# LTC4150_BOB.net
KiCad netlist of a schematic drawn in EAGLE
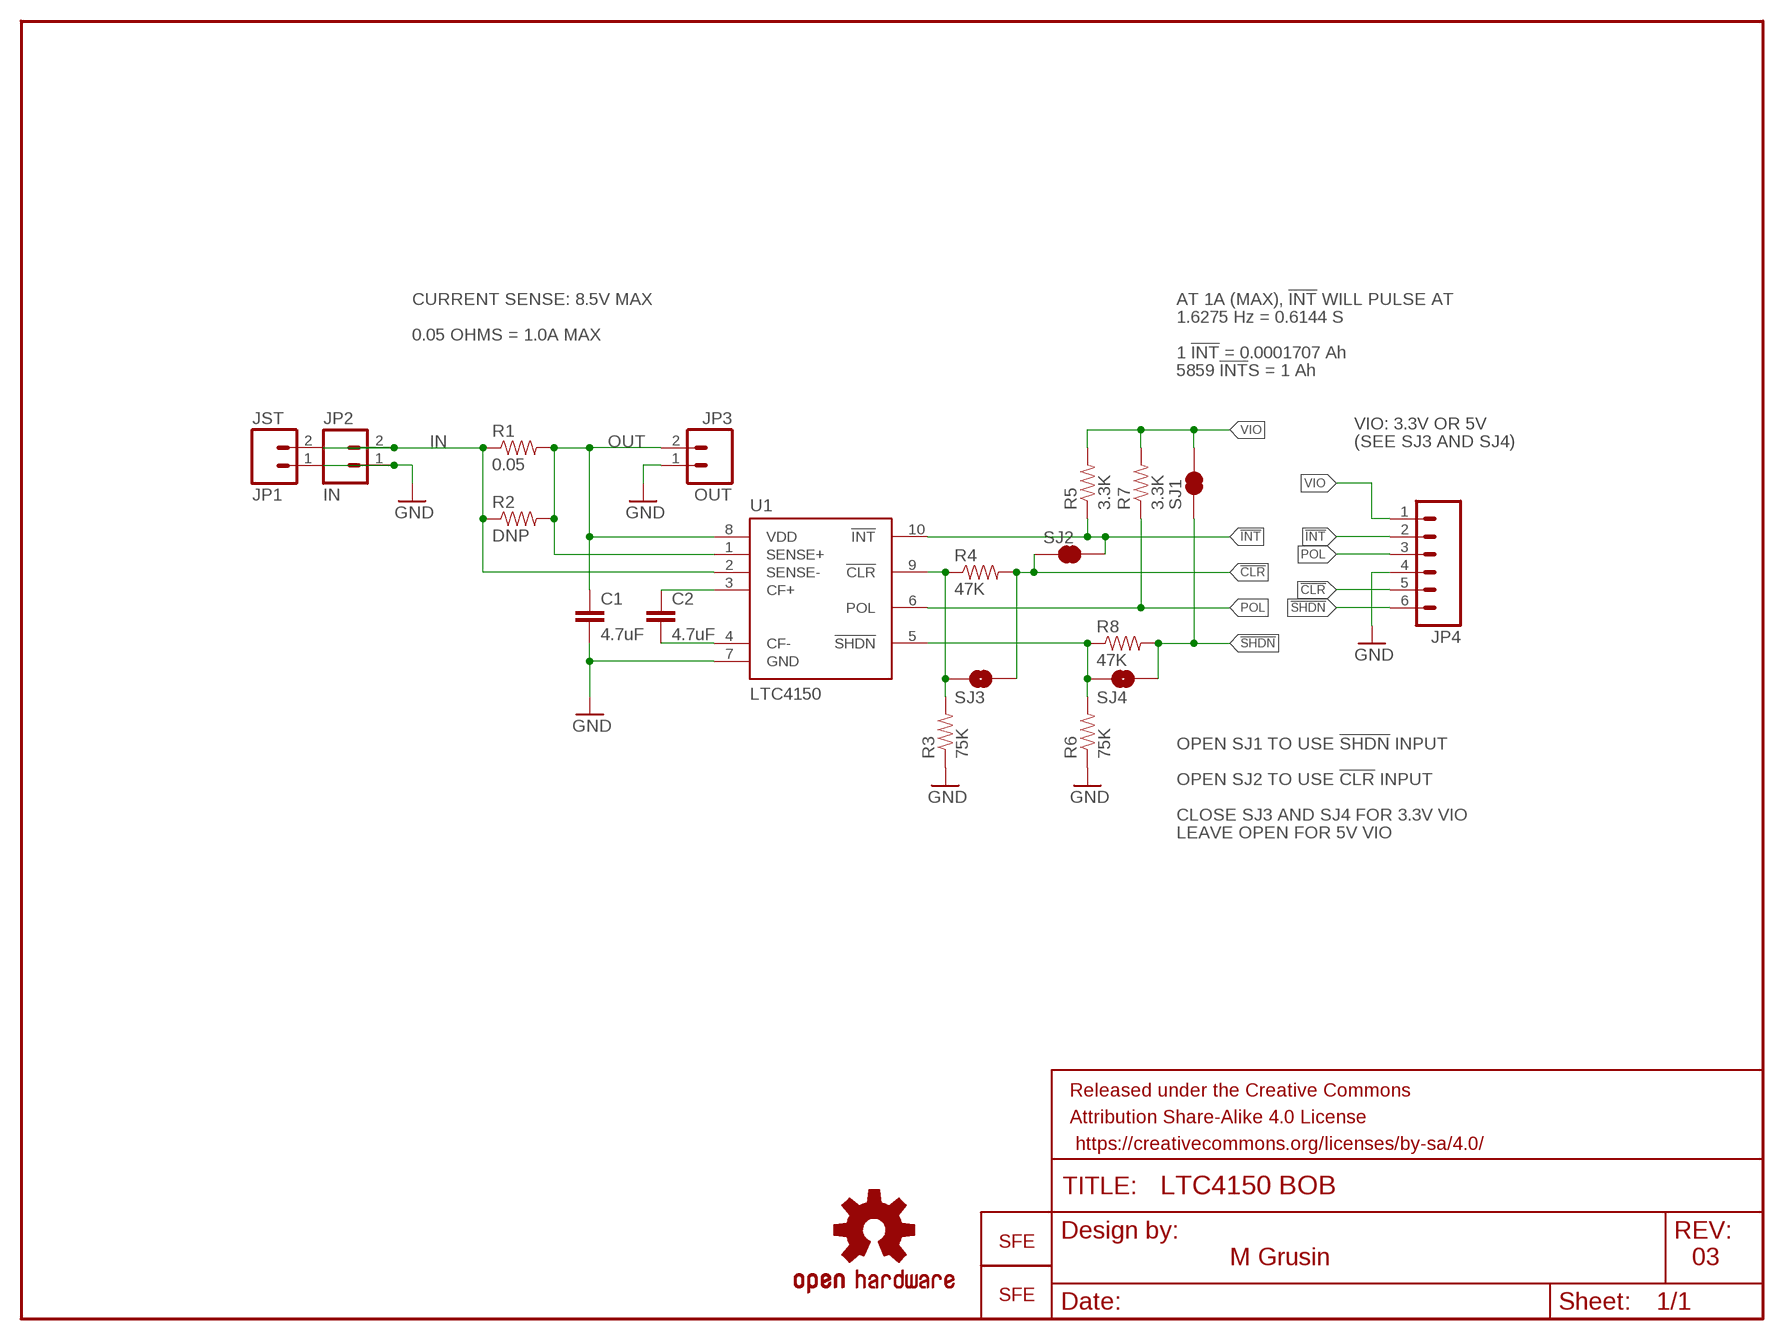
[diagram p0: schematic, sheet 1]

(export (version "E")
  (design (tool "Eeschema 10.0.6"))
  (components
    (comp (ref "C1")
      (value "4.7uF")
      (footprint "eagle-import:0603-CAP")
      (libsource (lib "eagle-import") (part "CAP0603-CAP"))
    )
    (comp (ref "C2")
      (value "4.7uF")
      (footprint "eagle-import:0603-CAP")
      (libsource (lib "eagle-import") (part "CAP0603-CAP"))
    )
    (comp (ref "FRAME1")
      (value "FRAME-LETTER")
      (footprint "eagle-import:CREATIVE_COMMONS")
      (libsource (lib "eagle-import") (part "FRAME-LETTER"))
    )
    (comp (ref "JP1")
      (value "JST")
      (footprint "eagle-import:JST-2-SMD")
      (libsource (lib "eagle-import") (part "M02-JST-2MM-SMT"))
    )
    (comp (ref "JP2")
      (value "IN")
      (footprint "eagle-import:1X02")
      (libsource (lib "eagle-import") (part "M02PTH"))
    )
    (comp (ref "JP3")
      (value "OUT")
      (footprint "eagle-import:1X02")
      (libsource (lib "eagle-import") (part "M02PTH"))
    )
    (comp (ref "JP4")
      (value "M06SIP")
      (footprint "eagle-import:1X06")
      (libsource (lib "eagle-import") (part "M06SIP"))
    )
    (comp (ref "LOGO1")
      (value "OSHW-LOGOS")
      (footprint "eagle-import:OSHW-LOGO-S")
      (libsource (lib "eagle-import") (part "OSHW-LOGOS"))
    )
    (comp (ref "LOGO2")
      (value "LOGO-SFENW2")
      (footprint "eagle-import:SFE-NEW-WEB")
      (libsource (lib "eagle-import") (part "LOGO-SFENW2"))
    )
    (comp (ref "LOGO3")
      (value "LOGO-SFESK")
      (footprint "eagle-import:SFE-LOGO-FLAME")
      (libsource (lib "eagle-import") (part "LOGO-SFESK"))
    )
    (comp (ref "R1")
      (value "0.05")
      (footprint "eagle-import:1206")
      (libsource (lib "eagle-import") (part "RESISTOR1206"))
    )
    (comp (ref "R2")
      (value "DNP")
      (footprint "eagle-import:AXIAL-0.3")
      (libsource (lib "eagle-import") (part "RESISTORAXIAL-0.3"))
    )
    (comp (ref "R3")
      (value "75K")
      (footprint "eagle-import:0603-RES")
      (libsource (lib "eagle-import") (part "RESISTOR0603-RES"))
    )
    (comp (ref "R4")
      (value "47K")
      (footprint "eagle-import:0603-RES")
      (libsource (lib "eagle-import") (part "RESISTOR0603-RES"))
    )
    (comp (ref "R5")
      (value "3.3K")
      (footprint "eagle-import:0603-RES")
      (libsource (lib "eagle-import") (part "RESISTOR0603-RES"))
    )
    (comp (ref "R6")
      (value "75K")
      (footprint "eagle-import:0603-RES")
      (libsource (lib "eagle-import") (part "RESISTOR0603-RES"))
    )
    (comp (ref "R7")
      (value "3.3K")
      (footprint "eagle-import:0603-RES")
      (libsource (lib "eagle-import") (part "RESISTOR0603-RES"))
    )
    (comp (ref "R8")
      (value "47K")
      (footprint "eagle-import:0603-RES")
      (libsource (lib "eagle-import") (part "RESISTOR0603-RES"))
    )
    (comp (ref "SJ1")
      (value "SOLDERJUMPERNC")
      (footprint "eagle-import:SJ_2S")
      (libsource (lib "eagle-import") (part "SOLDERJUMPERNC"))
    )
    (comp (ref "SJ2")
      (value "SOLDERJUMPERNC")
      (footprint "eagle-import:SJ_2S")
      (libsource (lib "eagle-import") (part "SOLDERJUMPERNC"))
    )
    (comp (ref "SJ3")
      (value "SOLDERJUMPERNO")
      (footprint "eagle-import:SJ_2S-NO")
      (libsource (lib "eagle-import") (part "SOLDERJUMPERNO"))
    )
    (comp (ref "SJ4")
      (value "SOLDERJUMPERNO")
      (footprint "eagle-import:SJ_2S-NO")
      (libsource (lib "eagle-import") (part "SOLDERJUMPERNO"))
    )
    (comp (ref "U1")
      (value "LTC4150")
      (footprint "eagle-import:MSOP10")
      (libsource (lib "eagle-import") (part "LTC4150"))
    )
  )
  (nets
    (net (code "1") (name "/IN") (class "Default")
      (node (ref "JP1") (pin "2") (pinfunction "1_2") (pintype "passive"))
      (node (ref "JP2") (pin "2") (pinfunction "2_2") (pintype "passive"))
      (node (ref "R1") (pin "1") (pinfunction "1_1") (pintype "passive"))
      (node (ref "R2") (pin "P$1") (pinfunction "1_P$1") (pintype "passive"))
      (node (ref "U1") (pin "2") (pinfunction "SENSE-_2") (pintype "bidirectional"))
    )
    (net (code "2") (name "/OUT") (class "Default")
      (node (ref "C1") (pin "1") (pinfunction "1_1") (pintype "passive"))
      (node (ref "JP3") (pin "2") (pinfunction "2_2") (pintype "passive"))
      (node (ref "R1") (pin "2") (pinfunction "2_2") (pintype "passive"))
      (node (ref "R2") (pin "P$2") (pinfunction "2_P$2") (pintype "passive"))
      (node (ref "U1") (pin "1") (pinfunction "SENSE+_1") (pintype "bidirectional"))
      (node (ref "U1") (pin "8") (pinfunction "VDD_8") (pintype "power_in"))
    )
    (net (code "3") (name "/~{CLR}") (class "Default")
      (node (ref "JP4") (pin "5") (pinfunction "5_5") (pintype "passive"))
      (node (ref "R4") (pin "2") (pinfunction "2_2") (pintype "passive"))
      (node (ref "SJ2") (pin "1") (pinfunction "1_1") (pintype "passive"))
      (node (ref "SJ3") (pin "2") (pinfunction "2_2") (pintype "passive"))
    )
    (net (code "4") (name "/~{INT}") (class "Default")
      (node (ref "JP4") (pin "2") (pinfunction "2_2") (pintype "passive"))
      (node (ref "R5") (pin "1") (pinfunction "1_1") (pintype "passive"))
      (node (ref "SJ2") (pin "2") (pinfunction "2_2") (pintype "passive"))
      (node (ref "U1") (pin "10") (pinfunction "~{INT}_10") (pintype "bidirectional"))
    )
    (net (code "5") (name "/~{SHDN}") (class "Default")
      (node (ref "JP4") (pin "6") (pinfunction "6_6") (pintype "passive"))
      (node (ref "R8") (pin "2") (pinfunction "2_2") (pintype "passive"))
      (node (ref "SJ1") (pin "2") (pinfunction "2_2") (pintype "passive"))
      (node (ref "SJ4") (pin "2") (pinfunction "2_2") (pintype "passive"))
    )
    (net (code "6") (name "GND") (class "Default")
      (node (ref "C1") (pin "2") (pinfunction "2_2") (pintype "passive"))
      (node (ref "JP1") (pin "1") (pinfunction "2_1") (pintype "passive"))
      (node (ref "JP2") (pin "1") (pinfunction "1_1") (pintype "passive"))
      (node (ref "JP3") (pin "1") (pinfunction "1_1") (pintype "passive"))
      (node (ref "JP4") (pin "4") (pinfunction "4_4") (pintype "passive"))
      (node (ref "R3") (pin "1") (pinfunction "1_1") (pintype "passive"))
      (node (ref "R6") (pin "1") (pinfunction "1_1") (pintype "passive"))
      (node (ref "U1") (pin "7") (pinfunction "GND_7") (pintype "power_in"))
    )
    (net (code "7") (name "Net-(U1-CF+)") (class "Default")
      (node (ref "C2") (pin "1") (pinfunction "1_1") (pintype "passive"))
      (node (ref "U1") (pin "3") (pinfunction "CF+_3") (pintype "bidirectional"))
    )
    (net (code "8") (name "Net-(U1-CF-)") (class "Default")
      (node (ref "C2") (pin "2") (pinfunction "2_2") (pintype "passive"))
      (node (ref "U1") (pin "4") (pinfunction "CF-_4") (pintype "bidirectional"))
    )
    (net (code "9") (name "Net-(U1-~{CLR})") (class "Default")
      (node (ref "R3") (pin "2") (pinfunction "2_2") (pintype "passive"))
      (node (ref "R4") (pin "1") (pinfunction "1_1") (pintype "passive"))
      (node (ref "SJ3") (pin "1") (pinfunction "1_1") (pintype "passive"))
      (node (ref "U1") (pin "9") (pinfunction "~{CLR}_9") (pintype "bidirectional"))
    )
    (net (code "10") (name "Net-(U1-~{SHDN})") (class "Default")
      (node (ref "R6") (pin "2") (pinfunction "2_2") (pintype "passive"))
      (node (ref "R8") (pin "1") (pinfunction "1_1") (pintype "passive"))
      (node (ref "SJ4") (pin "1") (pinfunction "1_1") (pintype "passive"))
      (node (ref "U1") (pin "5") (pinfunction "~{SHDN}_5") (pintype "input"))
    )
    (net (code "11") (name "POL") (class "Default")
      (node (ref "JP4") (pin "3") (pinfunction "3_3") (pintype "passive"))
      (node (ref "R7") (pin "1") (pinfunction "1_1") (pintype "passive"))
      (node (ref "U1") (pin "6") (pinfunction "POL_6") (pintype "bidirectional"))
    )
    (net (code "12") (name "VIO") (class "Default")
      (node (ref "JP4") (pin "1") (pinfunction "1_1") (pintype "passive"))
      (node (ref "R5") (pin "2") (pinfunction "2_2") (pintype "passive"))
      (node (ref "R7") (pin "2") (pinfunction "2_2") (pintype "passive"))
      (node (ref "SJ1") (pin "1") (pinfunction "1_1") (pintype "passive"))
    )
  )
)
